# ESP32_LED_Matrix.net
KiCad netlist of a schematic drawn in Altium Designer
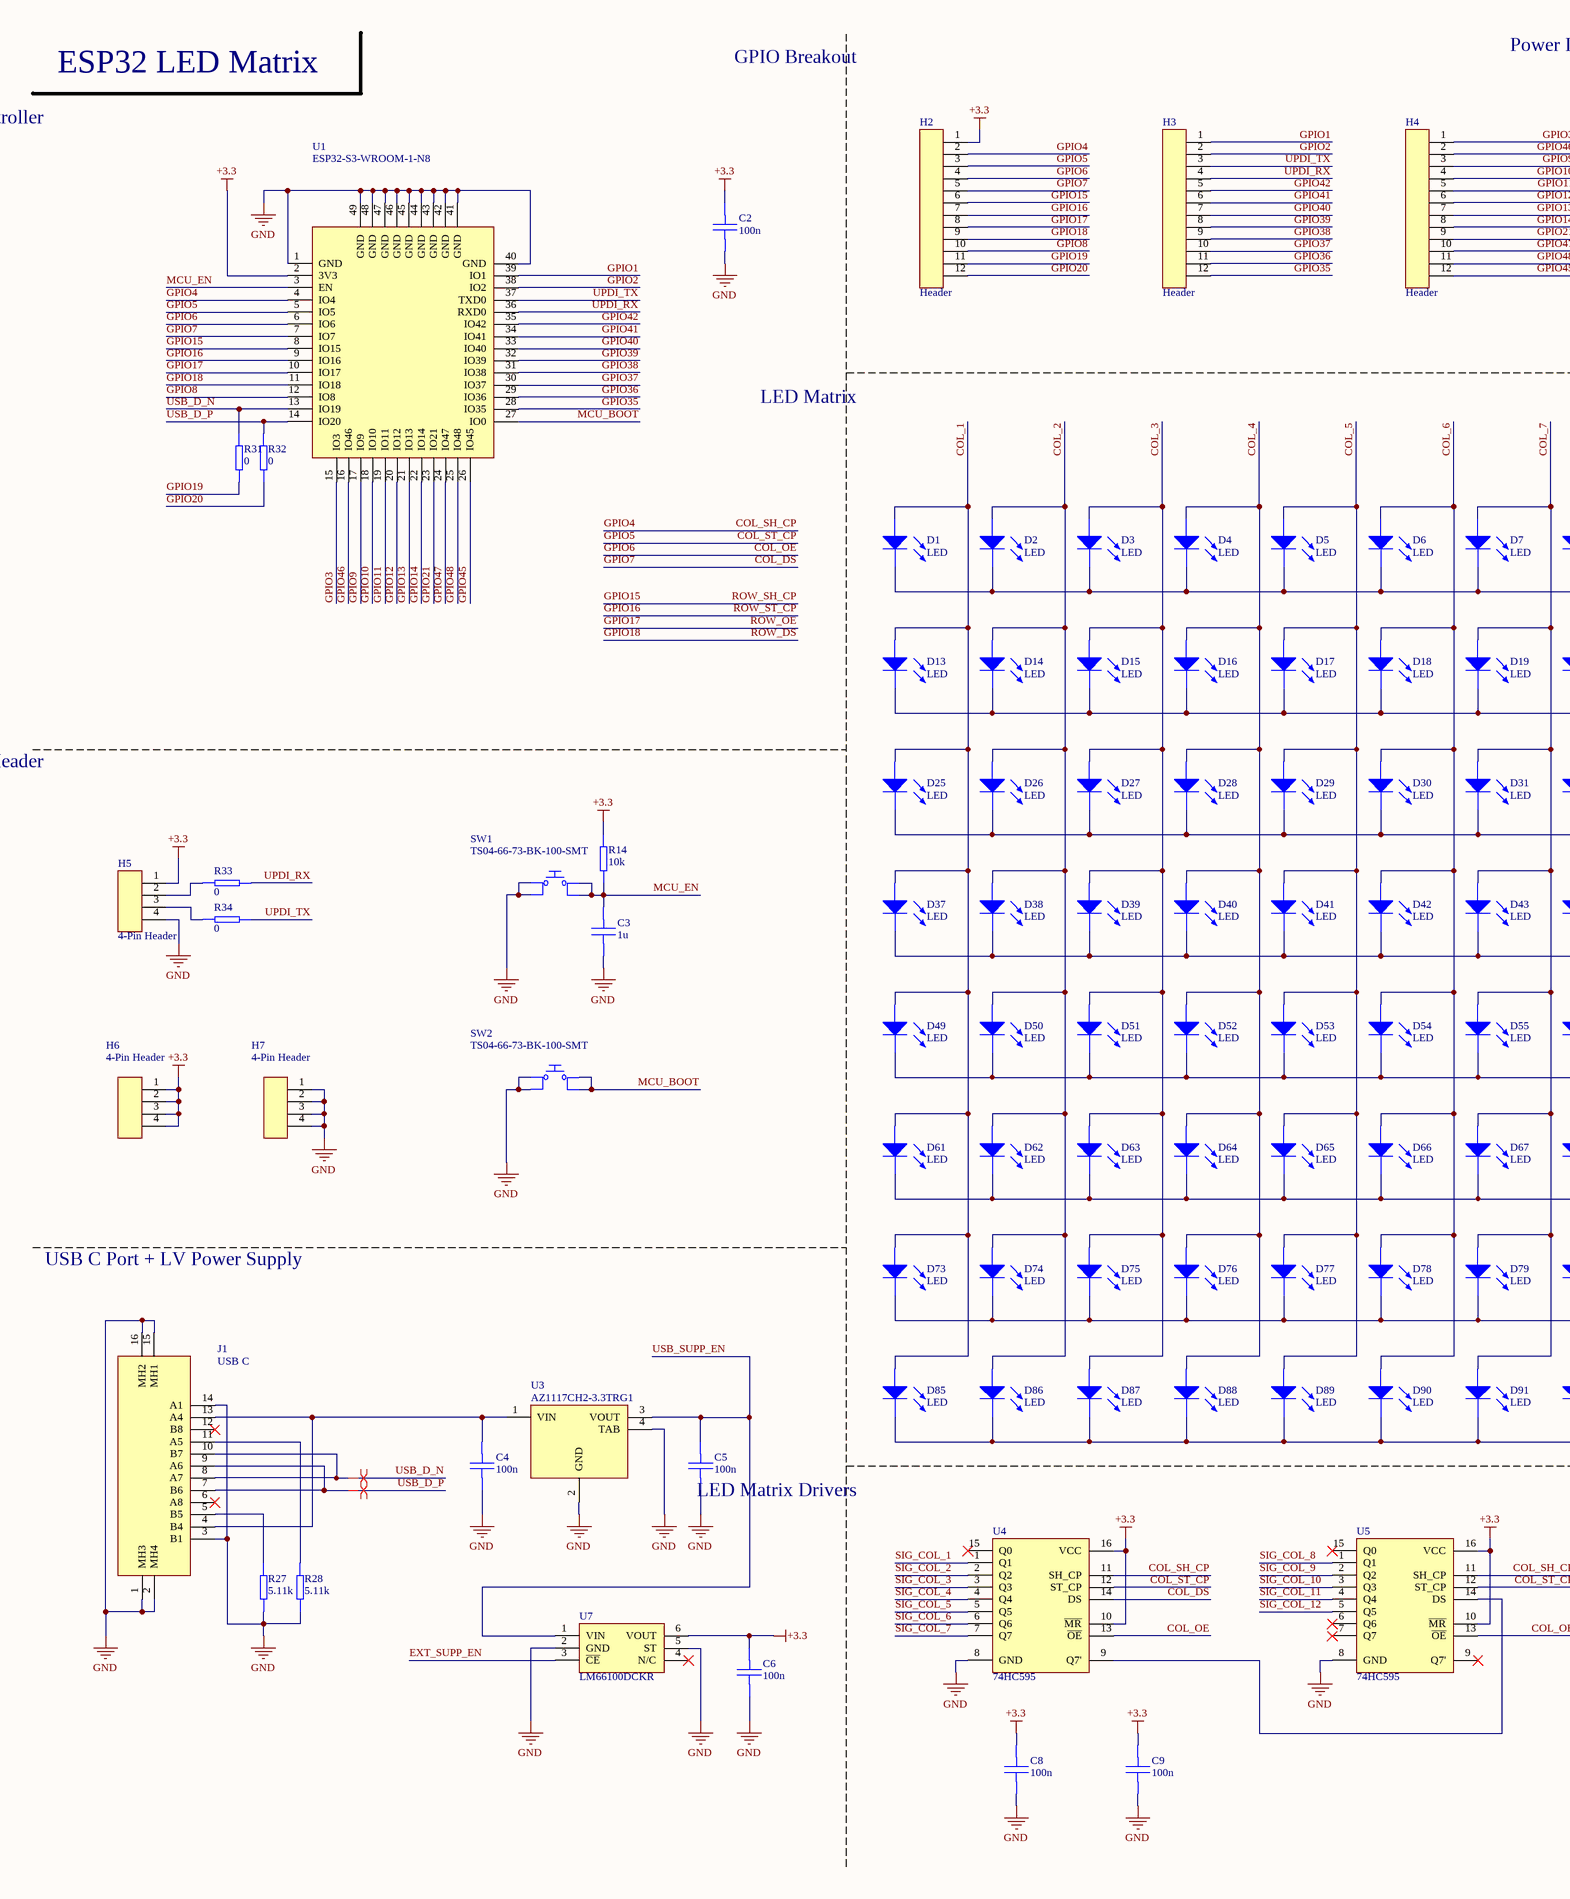
[diagram p0: ESP32_LED_Matrix.SchDoc, left]
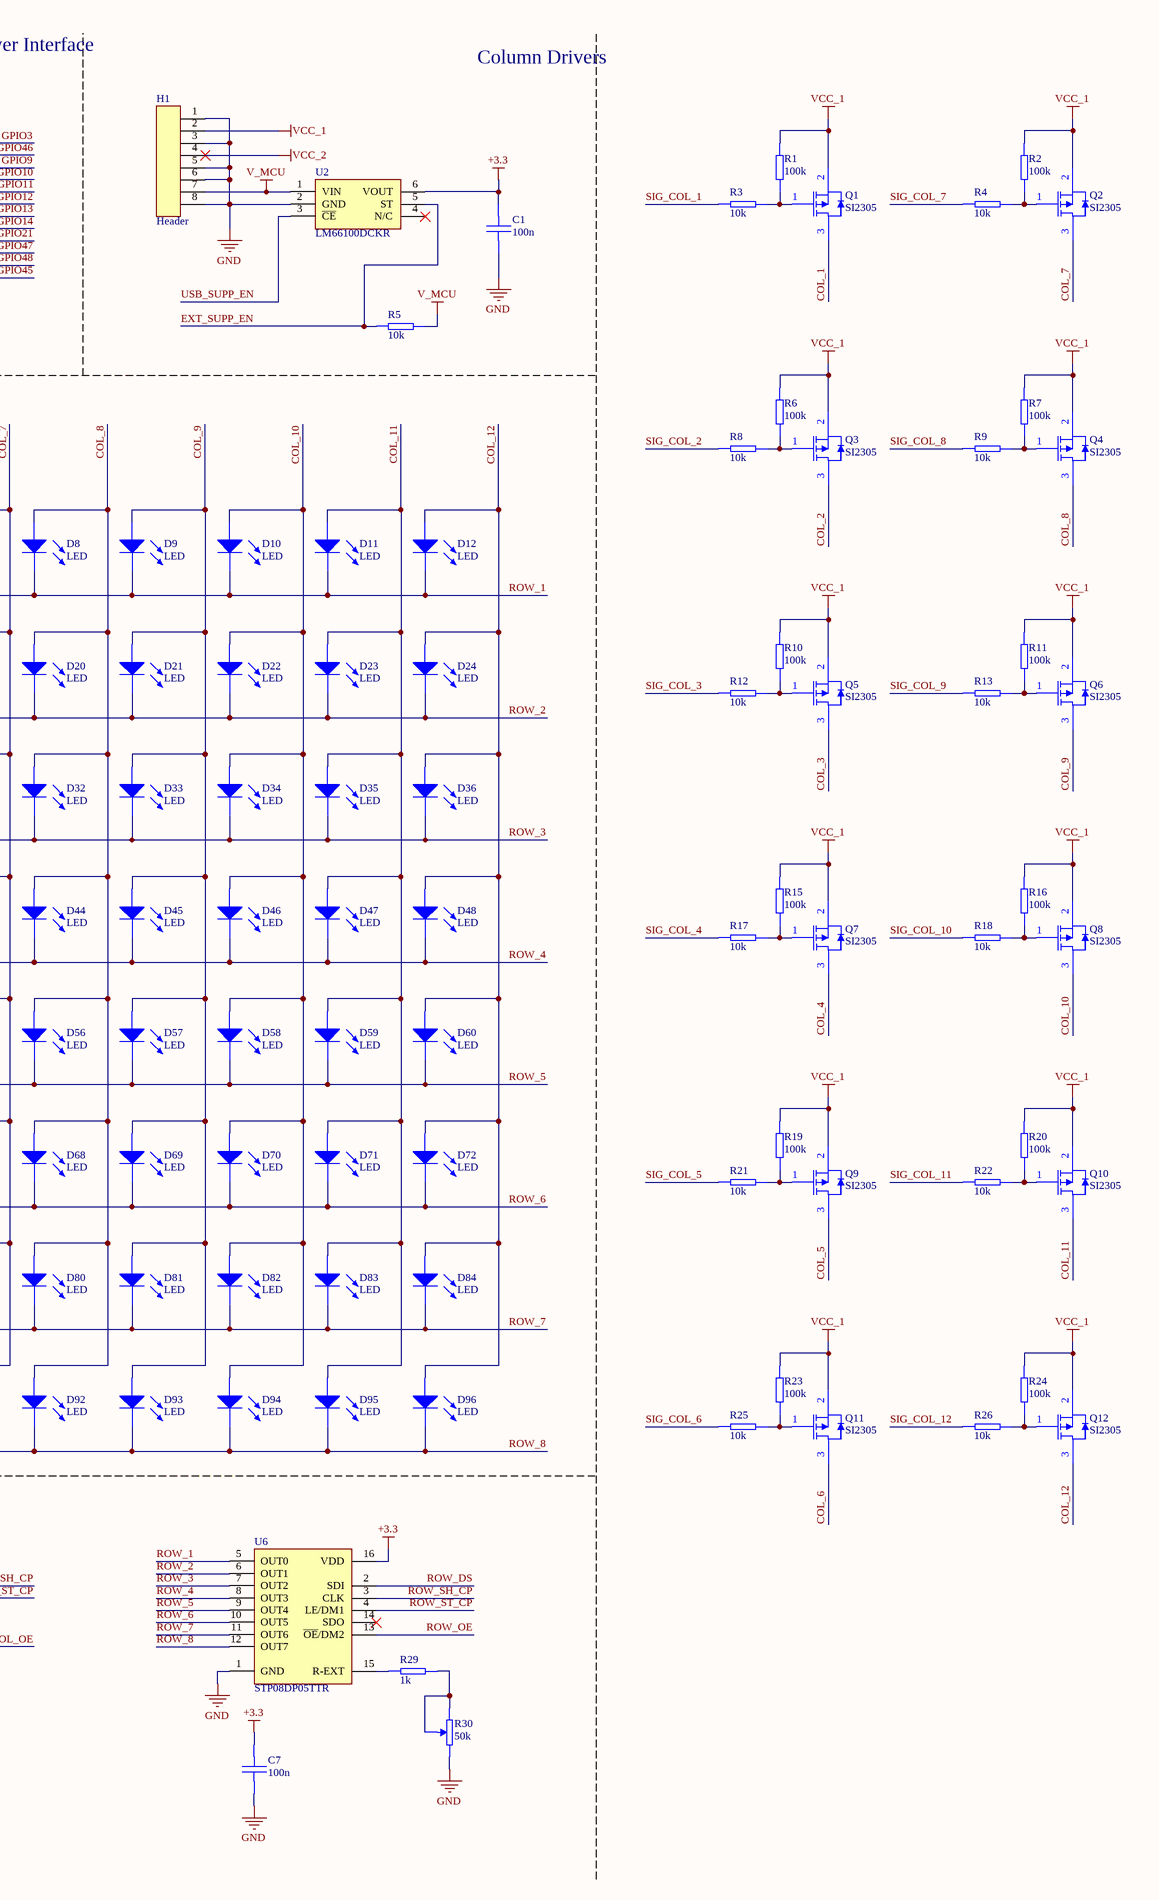
[diagram p1: ESP32_LED_Matrix.SchDoc, right]

(export (version "E")
  (design (tool "Eeschema 10.0.6"))
  (components
    (comp (ref "C1")
      (value "100n")
      (footprint "IEEE_Workshop_Footprints:CAP0805")
      (description "Non Polarized Capacitor")
      (libsource (lib "HT2.2") (part "Capacitor - Non Polarized"))
    )
    (comp (ref "C2")
      (value "100n")
      (footprint "IEEE_Workshop_Footprints:CAP0805")
      (description "Non Polarized Capacitor")
      (libsource (lib "HT2.2") (part "Capacitor - Non Polarized"))
    )
    (comp (ref "C3")
      (value "1u")
      (footprint "IEEE_Workshop_Footprints:CAP0805")
      (description "Non Polarized Capacitor")
      (libsource (lib "HT2.2") (part "Capacitor - Non Polarized"))
    )
    (comp (ref "C4")
      (value "100n")
      (footprint "IEEE_Workshop_Footprints:CAP0805")
      (description "Non Polarized Capacitor")
      (libsource (lib "TD") (part "Capacitor - Non Polarized"))
    )
    (comp (ref "C5")
      (value "100n")
      (footprint "IEEE_Workshop_Footprints:CAP0805")
      (description "Non Polarized Capacitor")
      (libsource (lib "HT2.2") (part "Capacitor - Non Polarized"))
    )
    (comp (ref "C6")
      (value "100n")
      (footprint "IEEE_Workshop_Footprints:CAP0805")
      (description "Non Polarized Capacitor")
      (libsource (lib "HT2.2") (part "Capacitor - Non Polarized"))
    )
    (comp (ref "C7")
      (value "100n")
      (footprint "IEEE_Workshop_Footprints:CAP0805")
      (description "Non Polarized Capacitor")
      (libsource (lib "TD") (part "Capacitor - Non Polarized"))
    )
    (comp (ref "C8")
      (value "100n")
      (footprint "IEEE_Workshop_Footprints:CAP0805")
      (description "Non Polarized Capacitor")
      (libsource (lib "TD") (part "Capacitor - Non Polarized"))
    )
    (comp (ref "C9")
      (value "100n")
      (footprint "IEEE_Workshop_Footprints:CAP0805")
      (description "Non Polarized Capacitor")
      (libsource (lib "TD") (part "Capacitor - Non Polarized"))
    )
    (comp (ref "D1")
      (value "LED")
      (footprint "IEEE_Workshop_Footprints:LEDM2012X80N")
      (description "General Purpose LED")
      (libsource (lib "TD") (part "LED"))
    )
    (comp (ref "D2")
      (value "LED")
      (footprint "IEEE_Workshop_Footprints:LEDM2012X80N")
      (description "General Purpose LED")
      (libsource (lib "TD") (part "LED"))
    )
    (comp (ref "D3")
      (value "LED")
      (footprint "IEEE_Workshop_Footprints:LEDM2012X80N")
      (description "General Purpose LED")
      (libsource (lib "TD") (part "LED"))
    )
    (comp (ref "D4")
      (value "LED")
      (footprint "IEEE_Workshop_Footprints:LEDM2012X80N")
      (description "General Purpose LED")
      (libsource (lib "TD") (part "LED"))
    )
    (comp (ref "D5")
      (value "LED")
      (footprint "IEEE_Workshop_Footprints:LEDM2012X80N")
      (description "General Purpose LED")
      (libsource (lib "TD") (part "LED"))
    )
    (comp (ref "D6")
      (value "LED")
      (footprint "IEEE_Workshop_Footprints:LEDM2012X80N")
      (description "General Purpose LED")
      (libsource (lib "TD") (part "LED"))
    )
    (comp (ref "D7")
      (value "LED")
      (footprint "IEEE_Workshop_Footprints:LEDM2012X80N")
      (description "General Purpose LED")
      (libsource (lib "TD") (part "LED"))
    )
    (comp (ref "D8")
      (value "LED")
      (footprint "IEEE_Workshop_Footprints:LEDM2012X80N")
      (description "General Purpose LED")
      (libsource (lib "TD") (part "LED"))
    )
    (comp (ref "D9")
      (value "LED")
      (footprint "IEEE_Workshop_Footprints:LEDM2012X80N")
      (description "General Purpose LED")
      (libsource (lib "TD") (part "LED"))
    )
    (comp (ref "D10")
      (value "LED")
      (footprint "IEEE_Workshop_Footprints:LEDM2012X80N")
      (description "General Purpose LED")
      (libsource (lib "TD") (part "LED"))
    )
    (comp (ref "D11")
      (value "LED")
      (footprint "IEEE_Workshop_Footprints:LEDM2012X80N")
      (description "General Purpose LED")
      (libsource (lib "TD") (part "LED"))
    )
    (comp (ref "D12")
      (value "LED")
      (footprint "IEEE_Workshop_Footprints:LEDM2012X80N")
      (description "General Purpose LED")
      (libsource (lib "TD") (part "LED"))
    )
    (comp (ref "D13")
      (value "LED")
      (footprint "IEEE_Workshop_Footprints:LEDM2012X80N")
      (description "General Purpose LED")
      (libsource (lib "TD") (part "LED"))
    )
    (comp (ref "D14")
      (value "LED")
      (footprint "IEEE_Workshop_Footprints:LEDM2012X80N")
      (description "General Purpose LED")
      (libsource (lib "TD") (part "LED"))
    )
    (comp (ref "D15")
      (value "LED")
      (footprint "IEEE_Workshop_Footprints:LEDM2012X80N")
      (description "General Purpose LED")
      (libsource (lib "TD") (part "LED"))
    )
    (comp (ref "D16")
      (value "LED")
      (footprint "IEEE_Workshop_Footprints:LEDM2012X80N")
      (description "General Purpose LED")
      (libsource (lib "TD") (part "LED"))
    )
    (comp (ref "D17")
      (value "LED")
      (footprint "IEEE_Workshop_Footprints:LEDM2012X80N")
      (description "General Purpose LED")
      (libsource (lib "TD") (part "LED"))
    )
    (comp (ref "D18")
      (value "LED")
      (footprint "IEEE_Workshop_Footprints:LEDM2012X80N")
      (description "General Purpose LED")
      (libsource (lib "TD") (part "LED"))
    )
    (comp (ref "D19")
      (value "LED")
      (footprint "IEEE_Workshop_Footprints:LEDM2012X80N")
      (description "General Purpose LED")
      (libsource (lib "TD") (part "LED"))
    )
    (comp (ref "D20")
      (value "LED")
      (footprint "IEEE_Workshop_Footprints:LEDM2012X80N")
      (description "General Purpose LED")
      (libsource (lib "TD") (part "LED"))
    )
    (comp (ref "D21")
      (value "LED")
      (footprint "IEEE_Workshop_Footprints:LEDM2012X80N")
      (description "General Purpose LED")
      (libsource (lib "TD") (part "LED"))
    )
    (comp (ref "D22")
      (value "LED")
      (footprint "IEEE_Workshop_Footprints:LEDM2012X80N")
      (description "General Purpose LED")
      (libsource (lib "TD") (part "LED"))
    )
    (comp (ref "D23")
      (value "LED")
      (footprint "IEEE_Workshop_Footprints:LEDM2012X80N")
      (description "General Purpose LED")
      (libsource (lib "TD") (part "LED"))
    )
    (comp (ref "D24")
      (value "LED")
      (footprint "IEEE_Workshop_Footprints:LEDM2012X80N")
      (description "General Purpose LED")
      (libsource (lib "TD") (part "LED"))
    )
    (comp (ref "D25")
      (value "LED")
      (footprint "IEEE_Workshop_Footprints:LEDM2012X80N")
      (description "General Purpose LED")
      (libsource (lib "TD") (part "LED"))
    )
    (comp (ref "D26")
      (value "LED")
      (footprint "IEEE_Workshop_Footprints:LEDM2012X80N")
      (description "General Purpose LED")
      (libsource (lib "TD") (part "LED"))
    )
    (comp (ref "D27")
      (value "LED")
      (footprint "IEEE_Workshop_Footprints:LEDM2012X80N")
      (description "General Purpose LED")
      (libsource (lib "TD") (part "LED"))
    )
    (comp (ref "D28")
      (value "LED")
      (footprint "IEEE_Workshop_Footprints:LEDM2012X80N")
      (description "General Purpose LED")
      (libsource (lib "TD") (part "LED"))
    )
    (comp (ref "D29")
      (value "LED")
      (footprint "IEEE_Workshop_Footprints:LEDM2012X80N")
      (description "General Purpose LED")
      (libsource (lib "TD") (part "LED"))
    )
    (comp (ref "D30")
      (value "LED")
      (footprint "IEEE_Workshop_Footprints:LEDM2012X80N")
      (description "General Purpose LED")
      (libsource (lib "TD") (part "LED"))
    )
    (comp (ref "D31")
      (value "LED")
      (footprint "IEEE_Workshop_Footprints:LEDM2012X80N")
      (description "General Purpose LED")
      (libsource (lib "TD") (part "LED"))
    )
    (comp (ref "D32")
      (value "LED")
      (footprint "IEEE_Workshop_Footprints:LEDM2012X80N")
      (description "General Purpose LED")
      (libsource (lib "TD") (part "LED"))
    )
    (comp (ref "D33")
      (value "LED")
      (footprint "IEEE_Workshop_Footprints:LEDM2012X80N")
      (description "General Purpose LED")
      (libsource (lib "TD") (part "LED"))
    )
    (comp (ref "D34")
      (value "LED")
      (footprint "IEEE_Workshop_Footprints:LEDM2012X80N")
      (description "General Purpose LED")
      (libsource (lib "TD") (part "LED"))
    )
    (comp (ref "D35")
      (value "LED")
      (footprint "IEEE_Workshop_Footprints:LEDM2012X80N")
      (description "General Purpose LED")
      (libsource (lib "TD") (part "LED"))
    )
    (comp (ref "D36")
      (value "LED")
      (footprint "IEEE_Workshop_Footprints:LEDM2012X80N")
      (description "General Purpose LED")
      (libsource (lib "TD") (part "LED"))
    )
    (comp (ref "D37")
      (value "LED")
      (footprint "IEEE_Workshop_Footprints:LEDM2012X80N")
      (description "General Purpose LED")
      (libsource (lib "TD") (part "LED"))
    )
    (comp (ref "D38")
      (value "LED")
      (footprint "IEEE_Workshop_Footprints:LEDM2012X80N")
      (description "General Purpose LED")
      (libsource (lib "TD") (part "LED"))
    )
    (comp (ref "D39")
      (value "LED")
      (footprint "IEEE_Workshop_Footprints:LEDM2012X80N")
      (description "General Purpose LED")
      (libsource (lib "TD") (part "LED"))
    )
    (comp (ref "D40")
      (value "LED")
      (footprint "IEEE_Workshop_Footprints:LEDM2012X80N")
      (description "General Purpose LED")
      (libsource (lib "TD") (part "LED"))
    )
    (comp (ref "D41")
      (value "LED")
      (footprint "IEEE_Workshop_Footprints:LEDM2012X80N")
      (description "General Purpose LED")
      (libsource (lib "TD") (part "LED"))
    )
    (comp (ref "D42")
      (value "LED")
      (footprint "IEEE_Workshop_Footprints:LEDM2012X80N")
      (description "General Purpose LED")
      (libsource (lib "TD") (part "LED"))
    )
    (comp (ref "D43")
      (value "LED")
      (footprint "IEEE_Workshop_Footprints:LEDM2012X80N")
      (description "General Purpose LED")
      (libsource (lib "TD") (part "LED"))
    )
    (comp (ref "D44")
      (value "LED")
      (footprint "IEEE_Workshop_Footprints:LEDM2012X80N")
      (description "General Purpose LED")
      (libsource (lib "TD") (part "LED"))
    )
    (comp (ref "D45")
      (value "LED")
      (footprint "IEEE_Workshop_Footprints:LEDM2012X80N")
      (description "General Purpose LED")
      (libsource (lib "TD") (part "LED"))
    )
    (comp (ref "D46")
      (value "LED")
      (footprint "IEEE_Workshop_Footprints:LEDM2012X80N")
      (description "General Purpose LED")
      (libsource (lib "TD") (part "LED"))
    )
    (comp (ref "D47")
      (value "LED")
      (footprint "IEEE_Workshop_Footprints:LEDM2012X80N")
      (description "General Purpose LED")
      (libsource (lib "TD") (part "LED"))
    )
    (comp (ref "D48")
      (value "LED")
      (footprint "IEEE_Workshop_Footprints:LEDM2012X80N")
      (description "General Purpose LED")
      (libsource (lib "TD") (part "LED"))
    )
    (comp (ref "D49")
      (value "LED")
      (footprint "IEEE_Workshop_Footprints:LEDM2012X80N")
      (description "General Purpose LED")
      (libsource (lib "TD") (part "LED"))
    )
    (comp (ref "D50")
      (value "LED")
      (footprint "IEEE_Workshop_Footprints:LEDM2012X80N")
      (description "General Purpose LED")
      (libsource (lib "TD") (part "LED"))
    )
    (comp (ref "D51")
      (value "LED")
      (footprint "IEEE_Workshop_Footprints:LEDM2012X80N")
      (description "General Purpose LED")
      (libsource (lib "TD") (part "LED"))
    )
    (comp (ref "D52")
      (value "LED")
      (footprint "IEEE_Workshop_Footprints:LEDM2012X80N")
      (description "General Purpose LED")
      (libsource (lib "TD") (part "LED"))
    )
    (comp (ref "D53")
      (value "LED")
      (footprint "IEEE_Workshop_Footprints:LEDM2012X80N")
      (description "General Purpose LED")
      (libsource (lib "TD") (part "LED"))
    )
    (comp (ref "D54")
      (value "LED")
      (footprint "IEEE_Workshop_Footprints:LEDM2012X80N")
      (description "General Purpose LED")
      (libsource (lib "TD") (part "LED"))
    )
    (comp (ref "D55")
      (value "LED")
      (footprint "IEEE_Workshop_Footprints:LEDM2012X80N")
      (description "General Purpose LED")
      (libsource (lib "TD") (part "LED"))
    )
    (comp (ref "D56")
      (value "LED")
      (footprint "IEEE_Workshop_Footprints:LEDM2012X80N")
      (description "General Purpose LED")
      (libsource (lib "TD") (part "LED"))
    )
    (comp (ref "D57")
      (value "LED")
      (footprint "IEEE_Workshop_Footprints:LEDM2012X80N")
      (description "General Purpose LED")
      (libsource (lib "TD") (part "LED"))
    )
    (comp (ref "D58")
      (value "LED")
      (footprint "IEEE_Workshop_Footprints:LEDM2012X80N")
      (description "General Purpose LED")
      (libsource (lib "TD") (part "LED"))
    )
    (comp (ref "D59")
      (value "LED")
      (footprint "IEEE_Workshop_Footprints:LEDM2012X80N")
      (description "General Purpose LED")
      (libsource (lib "TD") (part "LED"))
    )
    (comp (ref "D60")
      (value "LED")
      (footprint "IEEE_Workshop_Footprints:LEDM2012X80N")
      (description "General Purpose LED")
      (libsource (lib "TD") (part "LED"))
    )
    (comp (ref "D61")
      (value "LED")
      (footprint "IEEE_Workshop_Footprints:LEDM2012X80N")
      (description "General Purpose LED")
      (libsource (lib "TD") (part "LED"))
    )
    (comp (ref "D62")
      (value "LED")
      (footprint "IEEE_Workshop_Footprints:LEDM2012X80N")
      (description "General Purpose LED")
      (libsource (lib "TD") (part "LED"))
    )
    (comp (ref "D63")
      (value "LED")
      (footprint "IEEE_Workshop_Footprints:LEDM2012X80N")
      (description "General Purpose LED")
      (libsource (lib "TD") (part "LED"))
    )
    (comp (ref "D64")
      (value "LED")
      (footprint "IEEE_Workshop_Footprints:LEDM2012X80N")
      (description "General Purpose LED")
      (libsource (lib "TD") (part "LED"))
    )
    (comp (ref "D65")
      (value "LED")
      (footprint "IEEE_Workshop_Footprints:LEDM2012X80N")
      (description "General Purpose LED")
      (libsource (lib "TD") (part "LED"))
    )
    (comp (ref "D66")
      (value "LED")
      (footprint "IEEE_Workshop_Footprints:LEDM2012X80N")
      (description "General Purpose LED")
      (libsource (lib "TD") (part "LED"))
    )
    (comp (ref "D67")
      (value "LED")
      (footprint "IEEE_Workshop_Footprints:LEDM2012X80N")
      (description "General Purpose LED")
      (libsource (lib "TD") (part "LED"))
    )
    (comp (ref "D68")
      (value "LED")
      (footprint "IEEE_Workshop_Footprints:LEDM2012X80N")
      (description "General Purpose LED")
      (libsource (lib "TD") (part "LED"))
    )
    (comp (ref "D69")
      (value "LED")
      (footprint "IEEE_Workshop_Footprints:LEDM2012X80N")
      (description "General Purpose LED")
      (libsource (lib "TD") (part "LED"))
    )
    (comp (ref "D70")
      (value "LED")
      (footprint "IEEE_Workshop_Footprints:LEDM2012X80N")
      (description "General Purpose LED")
      (libsource (lib "TD") (part "LED"))
    )
    (comp (ref "D71")
      (value "LED")
      (footprint "IEEE_Workshop_Footprints:LEDM2012X80N")
      (description "General Purpose LED")
      (libsource (lib "TD") (part "LED"))
    )
    (comp (ref "D72")
      (value "LED")
      (footprint "IEEE_Workshop_Footprints:LEDM2012X80N")
      (description "General Purpose LED")
      (libsource (lib "TD") (part "LED"))
    )
    (comp (ref "D73")
      (value "LED")
      (footprint "IEEE_Workshop_Footprints:LEDM2012X80N")
      (description "General Purpose LED")
      (libsource (lib "TD") (part "LED"))
    )
    (comp (ref "D74")
      (value "LED")
      (footprint "IEEE_Workshop_Footprints:LEDM2012X80N")
      (description "General Purpose LED")
      (libsource (lib "TD") (part "LED"))
    )
    (comp (ref "D75")
      (value "LED")
      (footprint "IEEE_Workshop_Footprints:LEDM2012X80N")
      (description "General Purpose LED")
      (libsource (lib "TD") (part "LED"))
    )
    (comp (ref "D76")
      (value "LED")
      (footprint "IEEE_Workshop_Footprints:LEDM2012X80N")
      (description "General Purpose LED")
      (libsource (lib "TD") (part "LED"))
    )
    (comp (ref "D77")
      (value "LED")
      (footprint "IEEE_Workshop_Footprints:LEDM2012X80N")
      (description "General Purpose LED")
      (libsource (lib "TD") (part "LED"))
    )
    (comp (ref "D78")
      (value "LED")
      (footprint "IEEE_Workshop_Footprints:LEDM2012X80N")
      (description "General Purpose LED")
      (libsource (lib "TD") (part "LED"))
    )
    (comp (ref "D79")
      (value "LED")
      (footprint "IEEE_Workshop_Footprints:LEDM2012X80N")
      (description "General Purpose LED")
      (libsource (lib "TD") (part "LED"))
    )
    (comp (ref "D80")
      (value "LED")
      (footprint "IEEE_Workshop_Footprints:LEDM2012X80N")
      (description "General Purpose LED")
      (libsource (lib "TD") (part "LED"))
    )
    (comp (ref "D81")
      (value "LED")
      (footprint "IEEE_Workshop_Footprints:LEDM2012X80N")
      (description "General Purpose LED")
      (libsource (lib "TD") (part "LED"))
    )
    (comp (ref "D82")
      (value "LED")
      (footprint "IEEE_Workshop_Footprints:LEDM2012X80N")
      (description "General Purpose LED")
      (libsource (lib "TD") (part "LED"))
    )
    (comp (ref "D83")
      (value "LED")
      (footprint "IEEE_Workshop_Footprints:LEDM2012X80N")
      (description "General Purpose LED")
      (libsource (lib "TD") (part "LED"))
    )
    (comp (ref "D84")
      (value "LED")
      (footprint "IEEE_Workshop_Footprints:LEDM2012X80N")
      (description "General Purpose LED")
      (libsource (lib "TD") (part "LED"))
    )
    (comp (ref "D85")
      (value "LED")
      (footprint "IEEE_Workshop_Footprints:LEDM2012X80N")
      (description "General Purpose LED")
      (libsource (lib "TD") (part "LED"))
    )
    (comp (ref "D86")
      (value "LED")
      (footprint "IEEE_Workshop_Footprints:LEDM2012X80N")
      (description "General Purpose LED")
      (libsource (lib "TD") (part "LED"))
    )
    (comp (ref "D87")
      (value "LED")
      (footprint "IEEE_Workshop_Footprints:LEDM2012X80N")
      (description "General Purpose LED")
      (libsource (lib "TD") (part "LED"))
    )
    (comp (ref "D88")
      (value "LED")
      (footprint "IEEE_Workshop_Footprints:LEDM2012X80N")
      (description "General Purpose LED")
      (libsource (lib "TD") (part "LED"))
    )
    (comp (ref "D89")
      (value "LED")
      (footprint "IEEE_Workshop_Footprints:LEDM2012X80N")
      (description "General Purpose LED")
      (libsource (lib "TD") (part "LED"))
    )
    (comp (ref "D90")
      (value "LED")
      (footprint "IEEE_Workshop_Footprints:LEDM2012X80N")
      (description "General Purpose LED")
      (libsource (lib "TD") (part "LED"))
    )
    (comp (ref "D91")
      (value "LED")
      (footprint "IEEE_Workshop_Footprints:LEDM2012X80N")
      (description "General Purpose LED")
      (libsource (lib "TD") (part "LED"))
    )
    (comp (ref "D92")
      (value "LED")
      (footprint "IEEE_Workshop_Footprints:LEDM2012X80N")
      (description "General Purpose LED")
      (libsource (lib "TD") (part "LED"))
    )
    (comp (ref "D93")
      (value "LED")
      (footprint "IEEE_Workshop_Footprints:LEDM2012X80N")
      (description "General Purpose LED")
      (libsource (lib "TD") (part "LED"))
    )
    (comp (ref "D94")
      (value "LED")
      (footprint "IEEE_Workshop_Footprints:LEDM2012X80N")
      (description "General Purpose LED")
      (libsource (lib "TD") (part "LED"))
    )
    (comp (ref "D95")
      (value "LED")
      (footprint "IEEE_Workshop_Footprints:LEDM2012X80N")
      (description "General Purpose LED")
      (libsource (lib "TD") (part "LED"))
    )
    (comp (ref "D96")
      (value "LED")
      (footprint "IEEE_Workshop_Footprints:LEDM2012X80N")
      (description "General Purpose LED")
      (libsource (lib "TD") (part "LED"))
    )
    (comp (ref "H1")
      (value "Header")
      (footprint "IEEE_Workshop_Footprints:Header_1X8")
      (description "8-Pin Header")
      (libsource (lib "TD") (part "8-Pin Header"))
    )
    (comp (ref "H2")
      (value "Header")
      (footprint "IEEE_Workshop_Footprints:Header_1X12")
      (description "12-Pin Header")
      (libsource (lib "TD") (part "12-Pin Header"))
    )
    (comp (ref "H3")
      (value "Header")
      (footprint "IEEE_Workshop_Footprints:Header_1X12")
      (description "12-Pin Header")
      (libsource (lib "TD") (part "12-Pin Header"))
    )
    (comp (ref "H4")
      (value "Header")
      (footprint "IEEE_Workshop_Footprints:Header_1X12")
      (description "12-Pin Header")
      (libsource (lib "TD") (part "12-Pin Header"))
    )
    (comp (ref "H5")
      (value "4-Pin Header")
      (footprint "IEEE_Workshop_Footprints:Header_1X4")
      (libsource (lib "TD") (part "4-Pin Header"))
    )
    (comp (ref "H6")
      (value "4-Pin Header")
      (footprint "IEEE_Workshop_Footprints:Header_1X4")
      (libsource (lib "TD") (part "4-Pin Header"))
    )
    (comp (ref "H7")
      (value "4-Pin Header")
      (footprint "IEEE_Workshop_Footprints:Header_1X4")
      (libsource (lib "TD") (part "4-Pin Header"))
    )
    (comp (ref "J1")
      (value "USB C")
      (footprint "IEEE_Workshop_Footprints:USB TYPE C 12 PIN")
      (libsource (lib "TD") (part "USB Type C Connector 12 Pin"))
    )
    (comp (ref "Q1")
      (value "SI2305")
      (footprint "IEEE_Workshop_Footprints:SOT23")
      (description "General Purpose P-Channel MOSFET")
      (libsource (lib "TD") (part "SI2305"))
    )
    (comp (ref "Q2")
      (value "SI2305")
      (footprint "IEEE_Workshop_Footprints:SOT23")
      (description "General Purpose P-Channel MOSFET")
      (libsource (lib "TD") (part "SI2305"))
    )
    (comp (ref "Q3")
      (value "SI2305")
      (footprint "IEEE_Workshop_Footprints:SOT23")
      (description "General Purpose P-Channel MOSFET")
      (libsource (lib "TD") (part "SI2305"))
    )
    (comp (ref "Q4")
      (value "SI2305")
      (footprint "IEEE_Workshop_Footprints:SOT23")
      (description "General Purpose P-Channel MOSFET")
      (libsource (lib "TD") (part "SI2305"))
    )
    (comp (ref "Q5")
      (value "SI2305")
      (footprint "IEEE_Workshop_Footprints:SOT23")
      (description "General Purpose P-Channel MOSFET")
      (libsource (lib "TD") (part "SI2305"))
    )
    (comp (ref "Q6")
      (value "SI2305")
      (footprint "IEEE_Workshop_Footprints:SOT23")
      (description "General Purpose P-Channel MOSFET")
      (libsource (lib "TD") (part "SI2305"))
    )
    (comp (ref "Q7")
      (value "SI2305")
      (footprint "IEEE_Workshop_Footprints:SOT23")
      (description "General Purpose P-Channel MOSFET")
      (libsource (lib "TD") (part "SI2305"))
    )
    (comp (ref "Q8")
      (value "SI2305")
      (footprint "IEEE_Workshop_Footprints:SOT23")
      (description "General Purpose P-Channel MOSFET")
      (libsource (lib "TD") (part "SI2305"))
    )
    (comp (ref "Q9")
      (value "SI2305")
      (footprint "IEEE_Workshop_Footprints:SOT23")
      (description "General Purpose P-Channel MOSFET")
      (libsource (lib "TD") (part "SI2305"))
    )
    (comp (ref "Q10")
      (value "SI2305")
      (footprint "IEEE_Workshop_Footprints:SOT23")
      (description "General Purpose P-Channel MOSFET")
      (libsource (lib "TD") (part "SI2305"))
    )
    (comp (ref "Q11")
      (value "SI2305")
      (footprint "IEEE_Workshop_Footprints:SOT23")
      (description "General Purpose P-Channel MOSFET")
      (libsource (lib "TD") (part "SI2305"))
    )
    (comp (ref "Q12")
      (value "SI2305")
      (footprint "IEEE_Workshop_Footprints:SOT23")
      (description "General Purpose P-Channel MOSFET")
      (libsource (lib "TD") (part "SI2305"))
    )
    (comp (ref "R1")
      (value "100k")
      (footprint "IEEE_Workshop_Footprints:RESC0805")
      (description "Resistor")
      (libsource (lib "TD") (part "Resistor"))
    )
    (comp (ref "R2")
      (value "100k")
      (footprint "IEEE_Workshop_Footprints:RESC0805")
      (description "Resistor")
      (libsource (lib "TD") (part "Resistor"))
    )
    (comp (ref "R3")
      (value "10k")
      (footprint "IEEE_Workshop_Footprints:RESC0805")
      (description "Resistor")
      (libsource (lib "TD") (part "Resistor"))
    )
    (comp (ref "R4")
      (value "10k")
      (footprint "IEEE_Workshop_Footprints:RESC0805")
      (description "Resistor")
      (libsource (lib "TD") (part "Resistor"))
    )
    (comp (ref "R5")
      (value "10k")
      (footprint "IEEE_Workshop_Footprints:RESC0805")
      (description "Resistor")
      (libsource (lib "TD") (part "Resistor"))
    )
    (comp (ref "R6")
      (value "100k")
      (footprint "IEEE_Workshop_Footprints:RESC0805")
      (description "Resistor")
      (libsource (lib "TD") (part "Resistor"))
    )
    (comp (ref "R7")
      (value "100k")
      (footprint "IEEE_Workshop_Footprints:RESC0805")
      (description "Resistor")
      (libsource (lib "TD") (part "Resistor"))
    )
    (comp (ref "R8")
      (value "10k")
      (footprint "IEEE_Workshop_Footprints:RESC0805")
      (description "Resistor")
      (libsource (lib "TD") (part "Resistor"))
    )
    (comp (ref "R9")
      (value "10k")
      (footprint "IEEE_Workshop_Footprints:RESC0805")
      (description "Resistor")
      (libsource (lib "TD") (part "Resistor"))
    )
    (comp (ref "R10")
      (value "100k")
      (footprint "IEEE_Workshop_Footprints:RESC0805")
      (description "Resistor")
      (libsource (lib "TD") (part "Resistor"))
    )
    (comp (ref "R11")
      (value "100k")
      (footprint "IEEE_Workshop_Footprints:RESC0805")
      (description "Resistor")
      (libsource (lib "TD") (part "Resistor"))
    )
    (comp (ref "R12")
      (value "10k")
      (footprint "IEEE_Workshop_Footprints:RESC0805")
      (description "Resistor")
      (libsource (lib "TD") (part "Resistor"))
    )
    (comp (ref "R13")
      (value "10k")
      (footprint "IEEE_Workshop_Footprints:RESC0805")
      (description "Resistor")
      (libsource (lib "TD") (part "Resistor"))
    )
    (comp (ref "R14")
      (value "10k")
      (footprint "IEEE_Workshop_Footprints:RESC0805")
      (description "Resistor")
      (libsource (lib "TD") (part "Resistor"))
    )
    (comp (ref "R15")
      (value "100k")
      (footprint "IEEE_Workshop_Footprints:RESC0805")
      (description "Resistor")
      (libsource (lib "TD") (part "Resistor"))
    )
    (comp (ref "R16")
      (value "100k")
      (footprint "IEEE_Workshop_Footprints:RESC0805")
      (description "Resistor")
      (libsource (lib "TD") (part "Resistor"))
    )
    (comp (ref "R17")
      (value "10k")
      (footprint "IEEE_Workshop_Footprints:RESC0805")
      (description "Resistor")
      (libsource (lib "TD") (part "Resistor"))
    )
    (comp (ref "R18")
      (value "10k")
      (footprint "IEEE_Workshop_Footprints:RESC0805")
      (description "Resistor")
      (libsource (lib "TD") (part "Resistor"))
    )
    (comp (ref "R19")
      (value "100k")
      (footprint "IEEE_Workshop_Footprints:RESC0805")
      (description "Resistor")
      (libsource (lib "TD") (part "Resistor"))
    )
    (comp (ref "R20")
      (value "100k")
      (footprint "IEEE_Workshop_Footprints:RESC0805")
      (description "Resistor")
      (libsource (lib "TD") (part "Resistor"))
    )
    (comp (ref "R21")
      (value "10k")
      (footprint "IEEE_Workshop_Footprints:RESC0805")
      (description "Resistor")
      (libsource (lib "TD") (part "Resistor"))
    )
    (comp (ref "R22")
      (value "10k")
      (footprint "IEEE_Workshop_Footprints:RESC0805")
      (description "Resistor")
      (libsource (lib "TD") (part "Resistor"))
    )
    (comp (ref "R23")
      (value "100k")
      (footprint "IEEE_Workshop_Footprints:RESC0805")
      (description "Resistor")
      (libsource (lib "TD") (part "Resistor"))
    )
    (comp (ref "R24")
      (value "100k")
      (footprint "IEEE_Workshop_Footprints:RESC0805")
      (description "Resistor")
      (libsource (lib "TD") (part "Resistor"))
    )
    (comp (ref "R25")
      (value "10k")
      (footprint "IEEE_Workshop_Footprints:RESC0805")
      (description "Resistor")
      (libsource (lib "TD") (part "Resistor"))
    )
    (comp (ref "R26")
      (value "10k")
      (footprint "IEEE_Workshop_Footprints:RESC0805")
      (description "Resistor")
      (libsource (lib "TD") (part "Resistor"))
    )
    (comp (ref "R27")
      (value "5.11k")
      (footprint "IEEE_Workshop_Footprints:RESC0805")
      (description "Resistor")
      (libsource (lib "HT2.2") (part "Resistor"))
    )
    (comp (ref "R28")
      (value "5.11k")
      (footprint "IEEE_Workshop_Footprints:RESC0805")
      (description "Resistor")
      (libsource (lib "HT2.2") (part "Resistor"))
    )
    (comp (ref "R29")
      (value "1k")
      (footprint "IEEE_Workshop_Footprints:RESC0805")
      (description "Resistor")
      (libsource (lib "TD") (part "Resistor"))
    )
    (comp (ref "R30")
      (value "50k")
      (footprint "IEEE_Workshop_Footprints:3339P1103LF")
      (description "Potentionmeter")
      (libsource (lib "TD") (part "Potentiometer"))
    )
    (comp (ref "R31") (value "0") (description "Resistor") (libsource (lib "TD") (part "Resistor")))
    (comp (ref "R32") (value "0") (description "Resistor") (libsource (lib "TD") (part "Resistor")))
    (comp (ref "R33") (value "0") (description "Resistor") (libsource (lib "TD") (part "Resistor")))
    (comp (ref "R34") (value "0") (description "Resistor") (libsource (lib "TD") (part "Resistor")))
    (comp (ref "SW1")
      (value "TS04-66-73-BK-100-SMT")
      (footprint "IEEE_Workshop_Footprints:Tactile Button 6.0mm x 6.0mm")
      (description "Switch")
      (fields (field (name "MOUSER PART NUMBER") "179-TS046673BK100SMT"))
      (libsource (lib "TD") (part "TS04-66-73-BK-100-SMT"))
    )
    (comp (ref "SW2")
      (value "TS04-66-73-BK-100-SMT")
      (footprint "IEEE_Workshop_Footprints:Tactile Button 6.0mm x 6.0mm")
      (description "Switch")
      (fields (field (name "MOUSER PART NUMBER") "179-TS046673BK100SMT"))
      (libsource (lib "TD") (part "TS04-66-73-BK-100-SMT"))
    )
    (comp (ref "U1")
      (value "ESP32-S3-WROOM-1-N8")
      (footprint "IEEE_Workshop_Footprints:ESP32-S3-WROOM-1-N8")
      (description "ESP32 Microcontroller with Bluetooth and Wifi")
      (libsource (lib "HT2.3") (part "ESP32-S3-WROOM-1-N8"))
    )
    (comp (ref "U2")
      (value "LM66100DCKR")
      (footprint "IEEE_Workshop_Footprints:SC70-6")
      (description "5.5-V, 1.5-A 79-mΩ, Low IQ Ideal Diode With Input Polarity Protection")
      (fields (field (name "MOUSER PART NUMBER") "595-LM66100DCKR"))
      (libsource (lib "TD") (part "LM66100DCKR"))
    )
    (comp (ref "U3")
      (value "AZ1117CH2-3.3TRG1")
      (footprint "IEEE_Workshop_Footprints:SOT223")
      (description "3.3V Linear Voltage Regulator")
      (libsource (lib "TD") (part "AZ1117CH2-3.3TRG1_1"))
    )
    (comp (ref "U4")
      (value "74HC595")
      (footprint "IEEE_Workshop_Footprints:TSSOP16")
      (description "Shift Register")
      (libsource (lib "TD") (part "74HC595"))
    )
    (comp (ref "U5")
      (value "74HC595")
      (footprint "IEEE_Workshop_Footprints:TSSOP16")
      (description "Shift Register")
      (libsource (lib "TD") (part "74HC595"))
    )
    (comp (ref "U6")
      (value "STP08DP05TTR")
      (footprint "IEEE_Workshop_Footprints:TSSOP16")
      (description "LED Driver")
      (fields (field (name "MOUSER PART NUMBER") "511-STP08DP05TTR"))
      (libsource (lib "TD") (part "STP08DP05TTR"))
    )
    (comp (ref "U7")
      (value "LM66100DCKR")
      (footprint "IEEE_Workshop_Footprints:SC70-6")
      (description "5.5-V, 1.5-A 79-mΩ, Low IQ Ideal Diode With Input Polarity Protection")
      (fields (field (name "MOUSER PART NUMBER") "595-LM66100DCKR"))
      (libsource (lib "TD") (part "LM66100DCKR"))
    )
  )
  (nets
    (net (code "1") (name "+3.3") (class "Default")
      (node (ref "C1") (pin "1") (pintype "passive"))
      (node (ref "C2") (pin "1") (pintype "passive"))
      (node (ref "C6") (pin "1") (pintype "passive"))
      (node (ref "C7") (pin "1") (pintype "passive"))
      (node (ref "C8") (pin "1") (pintype "passive"))
      (node (ref "C9") (pin "1") (pintype "passive"))
      (node (ref "H2") (pin "1") (pintype "passive"))
      (node (ref "H5") (pin "1") (pintype "passive"))
      (node (ref "H6") (pin "1") (pintype "passive"))
      (node (ref "H6") (pin "2") (pintype "passive"))
      (node (ref "H6") (pin "3") (pintype "passive"))
      (node (ref "H6") (pin "4") (pintype "passive"))
      (node (ref "R14") (pin "1") (pintype "passive"))
      (node (ref "U1") (pin "2") (pinfunction "3V3_2") (pintype "passive"))
      (node (ref "U2") (pin "6") (pinfunction "VOUT_6") (pintype "passive"))
      (node (ref "U4") (pin "10") (pinfunction "~{MR}_10") (pintype "passive"))
      (node (ref "U4") (pin "16") (pinfunction "VCC_16") (pintype "passive"))
      (node (ref "U5") (pin "10") (pinfunction "~{MR}_10") (pintype "passive"))
      (node (ref "U5") (pin "16") (pinfunction "VCC_16") (pintype "passive"))
      (node (ref "U6") (pin "16") (pinfunction "VDD_16") (pintype "passive"))
      (node (ref "U7") (pin "6") (pinfunction "VOUT_6") (pintype "passive"))
    )
    (net (code "2") (name "/COL_1") (class "Default")
      (node (ref "D1") (pin "2") (pinfunction "A_2") (pintype "passive"))
      (node (ref "D13") (pin "2") (pinfunction "A_2") (pintype "passive"))
      (node (ref "D25") (pin "2") (pinfunction "A_2") (pintype "passive"))
      (node (ref "D37") (pin "2") (pinfunction "A_2") (pintype "passive"))
      (node (ref "D49") (pin "2") (pinfunction "A_2") (pintype "passive"))
      (node (ref "D61") (pin "2") (pinfunction "A_2") (pintype "passive"))
      (node (ref "D73") (pin "2") (pinfunction "A_2") (pintype "passive"))
      (node (ref "D85") (pin "2") (pinfunction "A_2") (pintype "passive"))
      (node (ref "Q1") (pin "3") (pinfunction "D_3") (pintype "passive"))
    )
    (net (code "3") (name "/COL_2") (class "Default")
      (node (ref "D14") (pin "2") (pinfunction "A_2") (pintype "passive"))
      (node (ref "D2") (pin "2") (pinfunction "A_2") (pintype "passive"))
      (node (ref "D26") (pin "2") (pinfunction "A_2") (pintype "passive"))
      (node (ref "D38") (pin "2") (pinfunction "A_2") (pintype "passive"))
      (node (ref "D50") (pin "2") (pinfunction "A_2") (pintype "passive"))
      (node (ref "D62") (pin "2") (pinfunction "A_2") (pintype "passive"))
      (node (ref "D74") (pin "2") (pinfunction "A_2") (pintype "passive"))
      (node (ref "D86") (pin "2") (pinfunction "A_2") (pintype "passive"))
      (node (ref "Q3") (pin "3") (pinfunction "D_3") (pintype "passive"))
    )
    (net (code "4") (name "/COL_3") (class "Default")
      (node (ref "D15") (pin "2") (pinfunction "A_2") (pintype "passive"))
      (node (ref "D27") (pin "2") (pinfunction "A_2") (pintype "passive"))
      (node (ref "D3") (pin "2") (pinfunction "A_2") (pintype "passive"))
      (node (ref "D39") (pin "2") (pinfunction "A_2") (pintype "passive"))
      (node (ref "D51") (pin "2") (pinfunction "A_2") (pintype "passive"))
      (node (ref "D63") (pin "2") (pinfunction "A_2") (pintype "passive"))
      (node (ref "D75") (pin "2") (pinfunction "A_2") (pintype "passive"))
      (node (ref "D87") (pin "2") (pinfunction "A_2") (pintype "passive"))
      (node (ref "Q5") (pin "3") (pinfunction "D_3") (pintype "passive"))
    )
    (net (code "5") (name "/COL_4") (class "Default")
      (node (ref "D16") (pin "2") (pinfunction "A_2") (pintype "passive"))
      (node (ref "D28") (pin "2") (pinfunction "A_2") (pintype "passive"))
      (node (ref "D4") (pin "2") (pinfunction "A_2") (pintype "passive"))
      (node (ref "D40") (pin "2") (pinfunction "A_2") (pintype "passive"))
      (node (ref "D52") (pin "2") (pinfunction "A_2") (pintype "passive"))
      (node (ref "D64") (pin "2") (pinfunction "A_2") (pintype "passive"))
      (node (ref "D76") (pin "2") (pinfunction "A_2") (pintype "passive"))
      (node (ref "D88") (pin "2") (pinfunction "A_2") (pintype "passive"))
      (node (ref "Q7") (pin "3") (pinfunction "D_3") (pintype "passive"))
    )
    (net (code "6") (name "/COL_5") (class "Default")
      (node (ref "D17") (pin "2") (pinfunction "A_2") (pintype "passive"))
      (node (ref "D29") (pin "2") (pinfunction "A_2") (pintype "passive"))
      (node (ref "D41") (pin "2") (pinfunction "A_2") (pintype "passive"))
      (node (ref "D5") (pin "2") (pinfunction "A_2") (pintype "passive"))
      (node (ref "D53") (pin "2") (pinfunction "A_2") (pintype "passive"))
      (node (ref "D65") (pin "2") (pinfunction "A_2") (pintype "passive"))
      (node (ref "D77") (pin "2") (pinfunction "A_2") (pintype "passive"))
      (node (ref "D89") (pin "2") (pinfunction "A_2") (pintype "passive"))
      (node (ref "Q9") (pin "3") (pinfunction "D_3") (pintype "passive"))
    )
    (net (code "7") (name "/COL_6") (class "Default")
      (node (ref "D18") (pin "2") (pinfunction "A_2") (pintype "passive"))
      (node (ref "D30") (pin "2") (pinfunction "A_2") (pintype "passive"))
      (node (ref "D42") (pin "2") (pinfunction "A_2") (pintype "passive"))
      (node (ref "D54") (pin "2") (pinfunction "A_2") (pintype "passive"))
      (node (ref "D6") (pin "2") (pinfunction "A_2") (pintype "passive"))
      (node (ref "D66") (pin "2") (pinfunction "A_2") (pintype "passive"))
      (node (ref "D78") (pin "2") (pinfunction "A_2") (pintype "passive"))
      (node (ref "D90") (pin "2") (pinfunction "A_2") (pintype "passive"))
      (node (ref "Q11") (pin "3") (pinfunction "D_3") (pintype "passive"))
    )
    (net (code "8") (name "/COL_7") (class "Default")
      (node (ref "D19") (pin "2") (pinfunction "A_2") (pintype "passive"))
      (node (ref "D31") (pin "2") (pinfunction "A_2") (pintype "passive"))
      (node (ref "D43") (pin "2") (pinfunction "A_2") (pintype "passive"))
      (node (ref "D55") (pin "2") (pinfunction "A_2") (pintype "passive"))
      (node (ref "D67") (pin "2") (pinfunction "A_2") (pintype "passive"))
      (node (ref "D7") (pin "2") (pinfunction "A_2") (pintype "passive"))
      (node (ref "D79") (pin "2") (pinfunction "A_2") (pintype "passive"))
      (node (ref "D91") (pin "2") (pinfunction "A_2") (pintype "passive"))
      (node (ref "Q2") (pin "3") (pinfunction "D_3") (pintype "passive"))
    )
    (net (code "9") (name "/COL_8") (class "Default")
      (node (ref "D20") (pin "2") (pinfunction "A_2") (pintype "passive"))
      (node (ref "D32") (pin "2") (pinfunction "A_2") (pintype "passive"))
      (node (ref "D44") (pin "2") (pinfunction "A_2") (pintype "passive"))
      (node (ref "D56") (pin "2") (pinfunction "A_2") (pintype "passive"))
      (node (ref "D68") (pin "2") (pinfunction "A_2") (pintype "passive"))
      (node (ref "D8") (pin "2") (pinfunction "A_2") (pintype "passive"))
      (node (ref "D80") (pin "2") (pinfunction "A_2") (pintype "passive"))
      (node (ref "D92") (pin "2") (pinfunction "A_2") (pintype "passive"))
      (node (ref "Q4") (pin "3") (pinfunction "D_3") (pintype "passive"))
    )
    (net (code "10") (name "/COL_9") (class "Default")
      (node (ref "D21") (pin "2") (pinfunction "A_2") (pintype "passive"))
      (node (ref "D33") (pin "2") (pinfunction "A_2") (pintype "passive"))
      (node (ref "D45") (pin "2") (pinfunction "A_2") (pintype "passive"))
      (node (ref "D57") (pin "2") (pinfunction "A_2") (pintype "passive"))
      (node (ref "D69") (pin "2") (pinfunction "A_2") (pintype "passive"))
      (node (ref "D81") (pin "2") (pinfunction "A_2") (pintype "passive"))
      (node (ref "D9") (pin "2") (pinfunction "A_2") (pintype "passive"))
      (node (ref "D93") (pin "2") (pinfunction "A_2") (pintype "passive"))
      (node (ref "Q6") (pin "3") (pinfunction "D_3") (pintype "passive"))
    )
    (net (code "11") (name "/COL_10") (class "Default")
      (node (ref "D10") (pin "2") (pinfunction "A_2") (pintype "passive"))
      (node (ref "D22") (pin "2") (pinfunction "A_2") (pintype "passive"))
      (node (ref "D34") (pin "2") (pinfunction "A_2") (pintype "passive"))
      (node (ref "D46") (pin "2") (pinfunction "A_2") (pintype "passive"))
      (node (ref "D58") (pin "2") (pinfunction "A_2") (pintype "passive"))
      (node (ref "D70") (pin "2") (pinfunction "A_2") (pintype "passive"))
      (node (ref "D82") (pin "2") (pinfunction "A_2") (pintype "passive"))
      (node (ref "D94") (pin "2") (pinfunction "A_2") (pintype "passive"))
      (node (ref "Q8") (pin "3") (pinfunction "D_3") (pintype "passive"))
    )
    (net (code "12") (name "/COL_11") (class "Default")
      (node (ref "D11") (pin "2") (pinfunction "A_2") (pintype "passive"))
      (node (ref "D23") (pin "2") (pinfunction "A_2") (pintype "passive"))
      (node (ref "D35") (pin "2") (pinfunction "A_2") (pintype "passive"))
      (node (ref "D47") (pin "2") (pinfunction "A_2") (pintype "passive"))
      (node (ref "D59") (pin "2") (pinfunction "A_2") (pintype "passive"))
      (node (ref "D71") (pin "2") (pinfunction "A_2") (pintype "passive"))
      (node (ref "D83") (pin "2") (pinfunction "A_2") (pintype "passive"))
      (node (ref "D95") (pin "2") (pinfunction "A_2") (pintype "passive"))
      (node (ref "Q10") (pin "3") (pinfunction "D_3") (pintype "passive"))
    )
    (net (code "13") (name "/COL_12") (class "Default")
      (node (ref "D12") (pin "2") (pinfunction "A_2") (pintype "passive"))
      (node (ref "D24") (pin "2") (pinfunction "A_2") (pintype "passive"))
      (node (ref "D36") (pin "2") (pinfunction "A_2") (pintype "passive"))
      (node (ref "D48") (pin "2") (pinfunction "A_2") (pintype "passive"))
      (node (ref "D60") (pin "2") (pinfunction "A_2") (pintype "passive"))
      (node (ref "D72") (pin "2") (pinfunction "A_2") (pintype "passive"))
      (node (ref "D84") (pin "2") (pinfunction "A_2") (pintype "passive"))
      (node (ref "D96") (pin "2") (pinfunction "A_2") (pintype "passive"))
      (node (ref "Q12") (pin "3") (pinfunction "D_3") (pintype "passive"))
    )
    (net (code "14") (name "/COL_DS") (class "Default")
      (node (ref "H2") (pin "5") (pintype "passive"))
      (node (ref "U1") (pin "7") (pinfunction "IO7_7") (pintype "passive"))
      (node (ref "U4") (pin "14") (pinfunction "DS_14") (pintype "passive"))
    )
    (net (code "15") (name "/COL_OE") (class "Default")
      (node (ref "H2") (pin "4") (pintype "passive"))
      (node (ref "U1") (pin "6") (pinfunction "IO6_6") (pintype "passive"))
      (node (ref "U4") (pin "13") (pinfunction "~{OE}_13") (pintype "passive"))
      (node (ref "U5") (pin "13") (pinfunction "~{OE}_13") (pintype "passive"))
    )
    (net (code "16") (name "/COL_SH_CP") (class "Default")
      (node (ref "H2") (pin "2") (pintype "passive"))
      (node (ref "U1") (pin "4") (pinfunction "IO4_4") (pintype "passive"))
      (node (ref "U4") (pin "11") (pinfunction "SH_CP_11") (pintype "passive"))
      (node (ref "U5") (pin "11") (pinfunction "SH_CP_11") (pintype "passive"))
    )
    (net (code "17") (name "/COL_ST_CP") (class "Default")
      (node (ref "H2") (pin "3") (pintype "passive"))
      (node (ref "U1") (pin "5") (pinfunction "IO5_5") (pintype "passive"))
      (node (ref "U4") (pin "12") (pinfunction "ST_CP_12") (pintype "passive"))
      (node (ref "U5") (pin "12") (pinfunction "ST_CP_12") (pintype "passive"))
    )
    (net (code "18") (name "/EXT_SUPP_EN") (class "Default")
      (node (ref "R5") (pin "1") (pintype "passive"))
      (node (ref "U2") (pin "5") (pinfunction "ST_5") (pintype "passive"))
      (node (ref "U7") (pin "3") (pinfunction "~{CE}_3") (pintype "passive"))
    )
    (net (code "19") (name "/GPIO1") (class "Default")
      (node (ref "H3") (pin "1") (pintype "passive"))
      (node (ref "U1") (pin "39") (pinfunction "IO1_39") (pintype "passive"))
    )
    (net (code "20") (name "/GPIO2") (class "Default")
      (node (ref "H3") (pin "2") (pintype "passive"))
      (node (ref "U1") (pin "38") (pinfunction "IO2_38") (pintype "passive"))
    )
    (net (code "21") (name "/GPIO3") (class "Default")
      (node (ref "H4") (pin "1") (pintype "passive"))
      (node (ref "U1") (pin "15") (pinfunction "IO3_15") (pintype "passive"))
    )
    (net (code "22") (name "/GPIO8") (class "Default")
      (node (ref "H2") (pin "10") (pintype "passive"))
      (node (ref "U1") (pin "12") (pinfunction "IO8_12") (pintype "passive"))
    )
    (net (code "23") (name "/GPIO9") (class "Default")
      (node (ref "H4") (pin "3") (pintype "passive"))
      (node (ref "U1") (pin "17") (pinfunction "IO9_17") (pintype "passive"))
    )
    (net (code "24") (name "/GPIO10") (class "Default")
      (node (ref "H4") (pin "4") (pintype "passive"))
      (node (ref "U1") (pin "18") (pinfunction "IO10_18") (pintype "passive"))
    )
    (net (code "25") (name "/GPIO11") (class "Default")
      (node (ref "H4") (pin "5") (pintype "passive"))
      (node (ref "U1") (pin "19") (pinfunction "IO11_19") (pintype "passive"))
    )
    (net (code "26") (name "/GPIO12") (class "Default")
      (node (ref "H4") (pin "6") (pintype "passive"))
      (node (ref "U1") (pin "20") (pinfunction "IO12_20") (pintype "passive"))
    )
    (net (code "27") (name "/GPIO13") (class "Default")
      (node (ref "H4") (pin "7") (pintype "passive"))
      (node (ref "U1") (pin "21") (pinfunction "IO13_21") (pintype "passive"))
    )
    (net (code "28") (name "/GPIO14") (class "Default")
      (node (ref "H4") (pin "8") (pintype "passive"))
      (node (ref "U1") (pin "22") (pinfunction "IO14_22") (pintype "passive"))
    )
    (net (code "29") (name "/GPIO15") (class "Default")
      (node (ref "H2") (pin "6") (pintype "passive"))
      (node (ref "U1") (pin "8") (pinfunction "IO15_8") (pintype "passive"))
      (node (ref "U6") (pin "3") (pinfunction "CLK_3") (pintype "passive"))
    )
    (net (code "30") (name "/GPIO16") (class "Default")
      (node (ref "H2") (pin "7") (pintype "passive"))
      (node (ref "U1") (pin "9") (pinfunction "IO16_9") (pintype "passive"))
      (node (ref "U6") (pin "4") (pinfunction "LE/DM1_4") (pintype "passive"))
    )
    (net (code "31") (name "/GPIO17") (class "Default")
      (node (ref "H2") (pin "8") (pintype "passive"))
      (node (ref "U1") (pin "10") (pinfunction "IO17_10") (pintype "passive"))
      (node (ref "U6") (pin "13") (pinfunction "~{OE}/DM2_13") (pintype "passive"))
    )
    (net (code "32") (name "/GPIO18") (class "Default")
      (node (ref "H2") (pin "9") (pintype "passive"))
      (node (ref "U1") (pin "11") (pinfunction "IO18_11") (pintype "passive"))
      (node (ref "U6") (pin "2") (pinfunction "SDI_2") (pintype "passive"))
    )
    (net (code "33") (name "/GPIO19") (class "Default")
      (node (ref "H2") (pin "11") (pintype "passive"))
      (node (ref "R31") (pin "1") (pintype "passive"))
    )
    (net (code "34") (name "/GPIO20") (class "Default")
      (node (ref "H2") (pin "12") (pintype "passive"))
      (node (ref "R32") (pin "1") (pintype "passive"))
    )
    (net (code "35") (name "/GPIO21") (class "Default")
      (node (ref "H4") (pin "9") (pintype "passive"))
      (node (ref "U1") (pin "23") (pinfunction "IO21_23") (pintype "passive"))
    )
    (net (code "36") (name "/GPIO35") (class "Default")
      (node (ref "H3") (pin "12") (pintype "passive"))
      (node (ref "U1") (pin "28") (pinfunction "IO35_28") (pintype "passive"))
    )
    (net (code "37") (name "/GPIO36") (class "Default")
      (node (ref "H3") (pin "11") (pintype "passive"))
      (node (ref "U1") (pin "29") (pinfunction "IO36_29") (pintype "passive"))
    )
    (net (code "38") (name "/GPIO37") (class "Default")
      (node (ref "H3") (pin "10") (pintype "passive"))
      (node (ref "U1") (pin "30") (pinfunction "IO37_30") (pintype "passive"))
    )
    (net (code "39") (name "/GPIO38") (class "Default")
      (node (ref "H3") (pin "9") (pintype "passive"))
      (node (ref "U1") (pin "31") (pinfunction "IO38_31") (pintype "passive"))
    )
    (net (code "40") (name "/GPIO39") (class "Default")
      (node (ref "H3") (pin "8") (pintype "passive"))
      (node (ref "U1") (pin "32") (pinfunction "IO39_32") (pintype "passive"))
    )
    (net (code "41") (name "/GPIO40") (class "Default")
      (node (ref "H3") (pin "7") (pintype "passive"))
      (node (ref "U1") (pin "33") (pinfunction "IO40_33") (pintype "passive"))
    )
    (net (code "42") (name "/GPIO41") (class "Default")
      (node (ref "H3") (pin "6") (pintype "passive"))
      (node (ref "U1") (pin "34") (pinfunction "IO41_34") (pintype "passive"))
    )
    (net (code "43") (name "/GPIO42") (class "Default")
      (node (ref "H3") (pin "5") (pintype "passive"))
      (node (ref "U1") (pin "35") (pinfunction "IO42_35") (pintype "passive"))
    )
    (net (code "44") (name "/GPIO45") (class "Default")
      (node (ref "H4") (pin "12") (pintype "passive"))
      (node (ref "U1") (pin "26") (pinfunction "IO45_26") (pintype "passive"))
    )
    (net (code "45") (name "/GPIO46") (class "Default")
      (node (ref "H4") (pin "2") (pintype "passive"))
      (node (ref "U1") (pin "16") (pinfunction "IO46_16") (pintype "passive"))
    )
    (net (code "46") (name "/GPIO47") (class "Default")
      (node (ref "H4") (pin "10") (pintype "passive"))
      (node (ref "U1") (pin "24") (pinfunction "IO47_24") (pintype "passive"))
    )
    (net (code "47") (name "/GPIO48") (class "Default")
      (node (ref "H4") (pin "11") (pintype "passive"))
      (node (ref "U1") (pin "25") (pinfunction "IO48_25") (pintype "passive"))
    )
    (net (code "48") (name "/MCU_BOOT") (class "Default")
      (node (ref "SW2") (pin "3") (pintype "passive"))
      (node (ref "SW2") (pin "4") (pintype "passive"))
      (node (ref "U1") (pin "27") (pinfunction "IO0_27") (pintype "passive"))
    )
    (net (code "49") (name "/MCU_EN") (class "Default")
      (node (ref "C3") (pin "1") (pintype "passive"))
      (node (ref "R14") (pin "2") (pintype "passive"))
      (node (ref "SW1") (pin "3") (pintype "passive"))
      (node (ref "SW1") (pin "4") (pintype "passive"))
      (node (ref "U1") (pin "3") (pinfunction "EN_3") (pintype "passive"))
    )
    (net (code "50") (name "/ROW_1") (class "Default")
      (node (ref "D1") (pin "1") (pinfunction "K_1") (pintype "passive"))
      (node (ref "D10") (pin "1") (pinfunction "K_1") (pintype "passive"))
      (node (ref "D11") (pin "1") (pinfunction "K_1") (pintype "passive"))
      (node (ref "D12") (pin "1") (pinfunction "K_1") (pintype "passive"))
      (node (ref "D2") (pin "1") (pinfunction "K_1") (pintype "passive"))
      (node (ref "D3") (pin "1") (pinfunction "K_1") (pintype "passive"))
      (node (ref "D4") (pin "1") (pinfunction "K_1") (pintype "passive"))
      (node (ref "D5") (pin "1") (pinfunction "K_1") (pintype "passive"))
      (node (ref "D6") (pin "1") (pinfunction "K_1") (pintype "passive"))
      (node (ref "D7") (pin "1") (pinfunction "K_1") (pintype "passive"))
      (node (ref "D8") (pin "1") (pinfunction "K_1") (pintype "passive"))
      (node (ref "D9") (pin "1") (pinfunction "K_1") (pintype "passive"))
      (node (ref "U6") (pin "5") (pinfunction "OUT0_5") (pintype "passive"))
    )
    (net (code "51") (name "/ROW_2") (class "Default")
      (node (ref "D13") (pin "1") (pinfunction "K_1") (pintype "passive"))
      (node (ref "D14") (pin "1") (pinfunction "K_1") (pintype "passive"))
      (node (ref "D15") (pin "1") (pinfunction "K_1") (pintype "passive"))
      (node (ref "D16") (pin "1") (pinfunction "K_1") (pintype "passive"))
      (node (ref "D17") (pin "1") (pinfunction "K_1") (pintype "passive"))
      (node (ref "D18") (pin "1") (pinfunction "K_1") (pintype "passive"))
      (node (ref "D19") (pin "1") (pinfunction "K_1") (pintype "passive"))
      (node (ref "D20") (pin "1") (pinfunction "K_1") (pintype "passive"))
      (node (ref "D21") (pin "1") (pinfunction "K_1") (pintype "passive"))
      (node (ref "D22") (pin "1") (pinfunction "K_1") (pintype "passive"))
      (node (ref "D23") (pin "1") (pinfunction "K_1") (pintype "passive"))
      (node (ref "D24") (pin "1") (pinfunction "K_1") (pintype "passive"))
      (node (ref "U6") (pin "6") (pinfunction "OUT1_6") (pintype "passive"))
    )
    (net (code "52") (name "/ROW_3") (class "Default")
      (node (ref "D25") (pin "1") (pinfunction "K_1") (pintype "passive"))
      (node (ref "D26") (pin "1") (pinfunction "K_1") (pintype "passive"))
      (node (ref "D27") (pin "1") (pinfunction "K_1") (pintype "passive"))
      (node (ref "D28") (pin "1") (pinfunction "K_1") (pintype "passive"))
      (node (ref "D29") (pin "1") (pinfunction "K_1") (pintype "passive"))
      (node (ref "D30") (pin "1") (pinfunction "K_1") (pintype "passive"))
      (node (ref "D31") (pin "1") (pinfunction "K_1") (pintype "passive"))
      (node (ref "D32") (pin "1") (pinfunction "K_1") (pintype "passive"))
      (node (ref "D33") (pin "1") (pinfunction "K_1") (pintype "passive"))
      (node (ref "D34") (pin "1") (pinfunction "K_1") (pintype "passive"))
      (node (ref "D35") (pin "1") (pinfunction "K_1") (pintype "passive"))
      (node (ref "D36") (pin "1") (pinfunction "K_1") (pintype "passive"))
      (node (ref "U6") (pin "7") (pinfunction "OUT2_7") (pintype "passive"))
    )
    (net (code "53") (name "/ROW_4") (class "Default")
      (node (ref "D37") (pin "1") (pinfunction "K_1") (pintype "passive"))
      (node (ref "D38") (pin "1") (pinfunction "K_1") (pintype "passive"))
      (node (ref "D39") (pin "1") (pinfunction "K_1") (pintype "passive"))
      (node (ref "D40") (pin "1") (pinfunction "K_1") (pintype "passive"))
      (node (ref "D41") (pin "1") (pinfunction "K_1") (pintype "passive"))
      (node (ref "D42") (pin "1") (pinfunction "K_1") (pintype "passive"))
      (node (ref "D43") (pin "1") (pinfunction "K_1") (pintype "passive"))
      (node (ref "D44") (pin "1") (pinfunction "K_1") (pintype "passive"))
      (node (ref "D45") (pin "1") (pinfunction "K_1") (pintype "passive"))
      (node (ref "D46") (pin "1") (pinfunction "K_1") (pintype "passive"))
      (node (ref "D47") (pin "1") (pinfunction "K_1") (pintype "passive"))
      (node (ref "D48") (pin "1") (pinfunction "K_1") (pintype "passive"))
      (node (ref "U6") (pin "8") (pinfunction "OUT3_8") (pintype "passive"))
    )
    (net (code "54") (name "/ROW_5") (class "Default")
      (node (ref "D49") (pin "1") (pinfunction "K_1") (pintype "passive"))
      (node (ref "D50") (pin "1") (pinfunction "K_1") (pintype "passive"))
      (node (ref "D51") (pin "1") (pinfunction "K_1") (pintype "passive"))
      (node (ref "D52") (pin "1") (pinfunction "K_1") (pintype "passive"))
      (node (ref "D53") (pin "1") (pinfunction "K_1") (pintype "passive"))
      (node (ref "D54") (pin "1") (pinfunction "K_1") (pintype "passive"))
      (node (ref "D55") (pin "1") (pinfunction "K_1") (pintype "passive"))
      (node (ref "D56") (pin "1") (pinfunction "K_1") (pintype "passive"))
      (node (ref "D57") (pin "1") (pinfunction "K_1") (pintype "passive"))
      (node (ref "D58") (pin "1") (pinfunction "K_1") (pintype "passive"))
      (node (ref "D59") (pin "1") (pinfunction "K_1") (pintype "passive"))
      (node (ref "D60") (pin "1") (pinfunction "K_1") (pintype "passive"))
      (node (ref "U6") (pin "9") (pinfunction "OUT4_9") (pintype "passive"))
    )
    (net (code "55") (name "/ROW_6") (class "Default")
      (node (ref "D61") (pin "1") (pinfunction "K_1") (pintype "passive"))
      (node (ref "D62") (pin "1") (pinfunction "K_1") (pintype "passive"))
      (node (ref "D63") (pin "1") (pinfunction "K_1") (pintype "passive"))
      (node (ref "D64") (pin "1") (pinfunction "K_1") (pintype "passive"))
      (node (ref "D65") (pin "1") (pinfunction "K_1") (pintype "passive"))
      (node (ref "D66") (pin "1") (pinfunction "K_1") (pintype "passive"))
      (node (ref "D67") (pin "1") (pinfunction "K_1") (pintype "passive"))
      (node (ref "D68") (pin "1") (pinfunction "K_1") (pintype "passive"))
      (node (ref "D69") (pin "1") (pinfunction "K_1") (pintype "passive"))
      (node (ref "D70") (pin "1") (pinfunction "K_1") (pintype "passive"))
      (node (ref "D71") (pin "1") (pinfunction "K_1") (pintype "passive"))
      (node (ref "D72") (pin "1") (pinfunction "K_1") (pintype "passive"))
      (node (ref "U6") (pin "10") (pinfunction "OUT5_10") (pintype "passive"))
    )
    (net (code "56") (name "/ROW_7") (class "Default")
      (node (ref "D73") (pin "1") (pinfunction "K_1") (pintype "passive"))
      (node (ref "D74") (pin "1") (pinfunction "K_1") (pintype "passive"))
      (node (ref "D75") (pin "1") (pinfunction "K_1") (pintype "passive"))
      (node (ref "D76") (pin "1") (pinfunction "K_1") (pintype "passive"))
      (node (ref "D77") (pin "1") (pinfunction "K_1") (pintype "passive"))
      (node (ref "D78") (pin "1") (pinfunction "K_1") (pintype "passive"))
      (node (ref "D79") (pin "1") (pinfunction "K_1") (pintype "passive"))
      (node (ref "D80") (pin "1") (pinfunction "K_1") (pintype "passive"))
      (node (ref "D81") (pin "1") (pinfunction "K_1") (pintype "passive"))
      (node (ref "D82") (pin "1") (pinfunction "K_1") (pintype "passive"))
      (node (ref "D83") (pin "1") (pinfunction "K_1") (pintype "passive"))
      (node (ref "D84") (pin "1") (pinfunction "K_1") (pintype "passive"))
      (node (ref "U6") (pin "11") (pinfunction "OUT6_11") (pintype "passive"))
    )
    (net (code "57") (name "/ROW_8") (class "Default")
      (node (ref "D85") (pin "1") (pinfunction "K_1") (pintype "passive"))
      (node (ref "D86") (pin "1") (pinfunction "K_1") (pintype "passive"))
      (node (ref "D87") (pin "1") (pinfunction "K_1") (pintype "passive"))
      (node (ref "D88") (pin "1") (pinfunction "K_1") (pintype "passive"))
      (node (ref "D89") (pin "1") (pinfunction "K_1") (pintype "passive"))
      (node (ref "D90") (pin "1") (pinfunction "K_1") (pintype "passive"))
      (node (ref "D91") (pin "1") (pinfunction "K_1") (pintype "passive"))
      (node (ref "D92") (pin "1") (pinfunction "K_1") (pintype "passive"))
      (node (ref "D93") (pin "1") (pinfunction "K_1") (pintype "passive"))
      (node (ref "D94") (pin "1") (pinfunction "K_1") (pintype "passive"))
      (node (ref "D95") (pin "1") (pinfunction "K_1") (pintype "passive"))
      (node (ref "D96") (pin "1") (pinfunction "K_1") (pintype "passive"))
      (node (ref "U6") (pin "12") (pinfunction "OUT7_12") (pintype "passive"))
    )
    (net (code "58") (name "/SIG_COL_1") (class "Default")
      (node (ref "R3") (pin "1") (pintype "passive"))
      (node (ref "U4") (pin "1") (pinfunction "Q1_1") (pintype "passive"))
    )
    (net (code "59") (name "/SIG_COL_2") (class "Default")
      (node (ref "R8") (pin "1") (pintype "passive"))
      (node (ref "U4") (pin "2") (pinfunction "Q2_2") (pintype "passive"))
    )
    (net (code "60") (name "/SIG_COL_3") (class "Default")
      (node (ref "R12") (pin "1") (pintype "passive"))
      (node (ref "U4") (pin "3") (pinfunction "Q3_3") (pintype "passive"))
    )
    (net (code "61") (name "/SIG_COL_4") (class "Default")
      (node (ref "R17") (pin "1") (pintype "passive"))
      (node (ref "U4") (pin "4") (pinfunction "Q4_4") (pintype "passive"))
    )
    (net (code "62") (name "/SIG_COL_5") (class "Default")
      (node (ref "R21") (pin "1") (pintype "passive"))
      (node (ref "U4") (pin "5") (pinfunction "Q5_5") (pintype "passive"))
    )
    (net (code "63") (name "/SIG_COL_6") (class "Default")
      (node (ref "R25") (pin "1") (pintype "passive"))
      (node (ref "U4") (pin "6") (pinfunction "Q6_6") (pintype "passive"))
    )
    (net (code "64") (name "/SIG_COL_7") (class "Default")
      (node (ref "R4") (pin "1") (pintype "passive"))
      (node (ref "U4") (pin "7") (pinfunction "Q7_7") (pintype "passive"))
    )
    (net (code "65") (name "/SIG_COL_8") (class "Default")
      (node (ref "R9") (pin "1") (pintype "passive"))
      (node (ref "U5") (pin "1") (pinfunction "Q1_1") (pintype "passive"))
    )
    (net (code "66") (name "/SIG_COL_9") (class "Default")
      (node (ref "R13") (pin "1") (pintype "passive"))
      (node (ref "U5") (pin "2") (pinfunction "Q2_2") (pintype "passive"))
    )
    (net (code "67") (name "/SIG_COL_10") (class "Default")
      (node (ref "R18") (pin "1") (pintype "passive"))
      (node (ref "U5") (pin "3") (pinfunction "Q3_3") (pintype "passive"))
    )
    (net (code "68") (name "/SIG_COL_11") (class "Default")
      (node (ref "R22") (pin "1") (pintype "passive"))
      (node (ref "U5") (pin "4") (pinfunction "Q4_4") (pintype "passive"))
    )
    (net (code "69") (name "/SIG_COL_12") (class "Default")
      (node (ref "R26") (pin "1") (pintype "passive"))
      (node (ref "U5") (pin "5") (pinfunction "Q5_5") (pintype "passive"))
    )
    (net (code "70") (name "/UPDI_RX") (class "Default")
      (node (ref "H3") (pin "4") (pintype "passive"))
      (node (ref "R33") (pin "1") (pintype "passive"))
      (node (ref "U1") (pin "36") (pinfunction "RXD0_36") (pintype "passive"))
    )
    (net (code "71") (name "/UPDI_TX") (class "Default")
      (node (ref "H3") (pin "3") (pintype "passive"))
      (node (ref "R34") (pin "1") (pintype "passive"))
      (node (ref "U1") (pin "37") (pinfunction "TXD0_37") (pintype "passive"))
    )
    (net (code "72") (name "/USB_D_N") (class "Default")
      (node (ref "J1") (pin "10") (pinfunction "B7_10") (pintype "passive"))
      (node (ref "J1") (pin "8") (pinfunction "A7_8") (pintype "passive"))
      (node (ref "R31") (pin "2") (pintype "passive"))
      (node (ref "U1") (pin "13") (pinfunction "IO19_13") (pintype "passive"))
    )
    (net (code "73") (name "/USB_D_P") (class "Default")
      (node (ref "J1") (pin "7") (pinfunction "B6_7") (pintype "passive"))
      (node (ref "J1") (pin "9") (pinfunction "A6_9") (pintype "passive"))
      (node (ref "R32") (pin "2") (pintype "passive"))
      (node (ref "U1") (pin "14") (pinfunction "IO20_14") (pintype "passive"))
    )
    (net (code "74") (name "/USB_SUPP_EN") (class "Default")
      (node (ref "C5") (pin "1") (pintype "passive"))
      (node (ref "U2") (pin "3") (pinfunction "~{CE}_3") (pintype "passive"))
      (node (ref "U3") (pin "3") (pinfunction "VOUT_3") (pintype "passive"))
      (node (ref "U7") (pin "1") (pinfunction "VIN_1") (pintype "passive"))
    )
    (net (code "75") (name "GND") (class "Default")
      (node (ref "C1") (pin "2") (pintype "passive"))
      (node (ref "C2") (pin "2") (pintype "passive"))
      (node (ref "C3") (pin "2") (pintype "passive"))
      (node (ref "C4") (pin "2") (pintype "passive"))
      (node (ref "C5") (pin "2") (pintype "passive"))
      (node (ref "C6") (pin "2") (pintype "passive"))
      (node (ref "C7") (pin "2") (pintype "passive"))
      (node (ref "C8") (pin "2") (pintype "passive"))
      (node (ref "C9") (pin "2") (pintype "passive"))
      (node (ref "H1") (pin "1") (pintype "passive"))
      (node (ref "H1") (pin "3") (pintype "passive"))
      (node (ref "H1") (pin "5") (pintype "passive"))
      (node (ref "H1") (pin "6") (pintype "passive"))
      (node (ref "H1") (pin "8") (pintype "passive"))
      (node (ref "H5") (pin "4") (pintype "passive"))
      (node (ref "H7") (pin "1") (pintype "passive"))
      (node (ref "H7") (pin "2") (pintype "passive"))
      (node (ref "H7") (pin "3") (pintype "passive"))
      (node (ref "H7") (pin "4") (pintype "passive"))
      (node (ref "J1") (pin "1") (pinfunction "MH3_1") (pintype "passive"))
      (node (ref "J1") (pin "14") (pinfunction "A1_14") (pintype "passive"))
      (node (ref "J1") (pin "15") (pinfunction "MH1_15") (pintype "passive"))
      (node (ref "J1") (pin "16") (pinfunction "MH2_16") (pintype "passive"))
      (node (ref "J1") (pin "2") (pinfunction "MH4_2") (pintype "passive"))
      (node (ref "J1") (pin "3") (pinfunction "B1_3") (pintype "passive"))
      (node (ref "R27") (pin "1") (pintype "passive"))
      (node (ref "R28") (pin "1") (pintype "passive"))
      (node (ref "R30") (pin "3") (pintype "passive"))
      (node (ref "SW1") (pin "1") (pintype "passive"))
      (node (ref "SW1") (pin "2") (pintype "passive"))
      (node (ref "SW2") (pin "1") (pintype "passive"))
      (node (ref "SW2") (pin "2") (pintype "passive"))
      (node (ref "U1") (pin "1") (pinfunction "GND_1") (pintype "passive"))
      (node (ref "U1") (pin "40") (pinfunction "GND_40") (pintype "passive"))
      (node (ref "U1") (pin "41") (pinfunction "GND_41") (pintype "passive"))
      (node (ref "U1") (pin "42") (pinfunction "GND_42") (pintype "passive"))
      (node (ref "U1") (pin "43") (pinfunction "GND_43") (pintype "passive"))
      (node (ref "U1") (pin "44") (pinfunction "GND_44") (pintype "passive"))
      (node (ref "U1") (pin "45") (pinfunction "GND_45") (pintype "passive"))
      (node (ref "U1") (pin "46") (pinfunction "GND_46") (pintype "passive"))
      (node (ref "U1") (pin "47") (pinfunction "GND_47") (pintype "passive"))
      (node (ref "U1") (pin "48") (pinfunction "GND_48") (pintype "passive"))
      (node (ref "U1") (pin "49") (pinfunction "GND_49") (pintype "passive"))
      (node (ref "U2") (pin "2") (pinfunction "GND_2") (pintype "passive"))
      (node (ref "U3") (pin "2") (pinfunction "GND_2") (pintype "passive"))
      (node (ref "U3") (pin "4") (pinfunction "TAB_4") (pintype "passive"))
      (node (ref "U4") (pin "8") (pinfunction "GND_8") (pintype "passive"))
      (node (ref "U5") (pin "8") (pinfunction "GND_8") (pintype "passive"))
      (node (ref "U6") (pin "1") (pinfunction "GND_1") (pintype "passive"))
      (node (ref "U7") (pin "2") (pinfunction "GND_2") (pintype "passive"))
      (node (ref "U7") (pin "5") (pinfunction "ST_5") (pintype "passive"))
    )
    (net (code "76") (name "Net-(H5-Pad2)") (class "Default")
      (node (ref "H5") (pin "2") (pintype "passive"))
      (node (ref "R33") (pin "2") (pintype "passive"))
    )
    (net (code "77") (name "Net-(H5-Pad3)") (class "Default")
      (node (ref "H5") (pin "3") (pintype "passive"))
      (node (ref "R34") (pin "2") (pintype "passive"))
    )
    (net (code "78") (name "Net-(J1-A4)") (class "Default")
      (node (ref "C4") (pin "1") (pintype "passive"))
      (node (ref "J1") (pin "13") (pinfunction "A4_13") (pintype "passive"))
      (node (ref "J1") (pin "4") (pinfunction "B4_4") (pintype "passive"))
      (node (ref "U3") (pin "1") (pinfunction "VIN_1") (pintype "passive"))
    )
    (net (code "79") (name "Net-(J1-A5)") (class "Default")
      (node (ref "J1") (pin "11") (pinfunction "A5_11") (pintype "passive"))
      (node (ref "R28") (pin "2") (pintype "passive"))
    )
    (net (code "80") (name "Net-(J1-B5)") (class "Default")
      (node (ref "J1") (pin "5") (pinfunction "B5_5") (pintype "passive"))
      (node (ref "R27") (pin "2") (pintype "passive"))
    )
    (net (code "81") (name "Net-(Q1-G)") (class "Default")
      (node (ref "Q1") (pin "1") (pinfunction "G_1") (pintype "passive"))
      (node (ref "R1") (pin "2") (pintype "passive"))
      (node (ref "R3") (pin "2") (pintype "passive"))
    )
    (net (code "82") (name "Net-(Q2-G)") (class "Default")
      (node (ref "Q2") (pin "1") (pinfunction "G_1") (pintype "passive"))
      (node (ref "R2") (pin "2") (pintype "passive"))
      (node (ref "R4") (pin "2") (pintype "passive"))
    )
    (net (code "83") (name "Net-(Q3-G)") (class "Default")
      (node (ref "Q3") (pin "1") (pinfunction "G_1") (pintype "passive"))
      (node (ref "R6") (pin "2") (pintype "passive"))
      (node (ref "R8") (pin "2") (pintype "passive"))
    )
    (net (code "84") (name "Net-(Q4-G)") (class "Default")
      (node (ref "Q4") (pin "1") (pinfunction "G_1") (pintype "passive"))
      (node (ref "R7") (pin "2") (pintype "passive"))
      (node (ref "R9") (pin "2") (pintype "passive"))
    )
    (net (code "85") (name "Net-(Q5-G)") (class "Default")
      (node (ref "Q5") (pin "1") (pinfunction "G_1") (pintype "passive"))
      (node (ref "R10") (pin "2") (pintype "passive"))
      (node (ref "R12") (pin "2") (pintype "passive"))
    )
    (net (code "86") (name "Net-(Q6-G)") (class "Default")
      (node (ref "Q6") (pin "1") (pinfunction "G_1") (pintype "passive"))
      (node (ref "R11") (pin "2") (pintype "passive"))
      (node (ref "R13") (pin "2") (pintype "passive"))
    )
    (net (code "87") (name "Net-(Q7-G)") (class "Default")
      (node (ref "Q7") (pin "1") (pinfunction "G_1") (pintype "passive"))
      (node (ref "R15") (pin "2") (pintype "passive"))
      (node (ref "R17") (pin "2") (pintype "passive"))
    )
    (net (code "88") (name "Net-(Q8-G)") (class "Default")
      (node (ref "Q8") (pin "1") (pinfunction "G_1") (pintype "passive"))
      (node (ref "R16") (pin "2") (pintype "passive"))
      (node (ref "R18") (pin "2") (pintype "passive"))
    )
    (net (code "89") (name "Net-(Q9-G)") (class "Default")
      (node (ref "Q9") (pin "1") (pinfunction "G_1") (pintype "passive"))
      (node (ref "R19") (pin "2") (pintype "passive"))
      (node (ref "R21") (pin "2") (pintype "passive"))
    )
    (net (code "90") (name "Net-(Q10-G)") (class "Default")
      (node (ref "Q10") (pin "1") (pinfunction "G_1") (pintype "passive"))
      (node (ref "R20") (pin "2") (pintype "passive"))
      (node (ref "R22") (pin "2") (pintype "passive"))
    )
    (net (code "91") (name "Net-(Q11-G)") (class "Default")
      (node (ref "Q11") (pin "1") (pinfunction "G_1") (pintype "passive"))
      (node (ref "R23") (pin "2") (pintype "passive"))
      (node (ref "R25") (pin "2") (pintype "passive"))
    )
    (net (code "92") (name "Net-(Q12-G)") (class "Default")
      (node (ref "Q12") (pin "1") (pinfunction "G_1") (pintype "passive"))
      (node (ref "R24") (pin "2") (pintype "passive"))
      (node (ref "R26") (pin "2") (pintype "passive"))
    )
    (net (code "93") (name "Net-(R29-Pad2)") (class "Default")
      (node (ref "R29") (pin "2") (pintype "passive"))
      (node (ref "R30") (pin "1") (pintype "passive"))
      (node (ref "R30") (pin "2") (pintype "passive"))
    )
    (net (code "94") (name "Net-(U4-Q7')") (class "Default")
      (node (ref "U4") (pin "9") (pinfunction "Q7'_9") (pintype "passive"))
      (node (ref "U5") (pin "14") (pinfunction "DS_14") (pintype "passive"))
    )
    (net (code "95") (name "Net-(U6-R-EXT)") (class "Default")
      (node (ref "R29") (pin "1") (pintype "passive"))
      (node (ref "U6") (pin "15") (pinfunction "R-EXT_15") (pintype "passive"))
    )
    (net (code "96") (name "VCC_1") (class "Default")
      (node (ref "H1") (pin "2") (pintype "passive"))
      (node (ref "Q1") (pin "2") (pinfunction "S_2") (pintype "passive"))
      (node (ref "Q10") (pin "2") (pinfunction "S_2") (pintype "passive"))
      (node (ref "Q11") (pin "2") (pinfunction "S_2") (pintype "passive"))
      (node (ref "Q12") (pin "2") (pinfunction "S_2") (pintype "passive"))
      (node (ref "Q2") (pin "2") (pinfunction "S_2") (pintype "passive"))
      (node (ref "Q3") (pin "2") (pinfunction "S_2") (pintype "passive"))
      (node (ref "Q4") (pin "2") (pinfunction "S_2") (pintype "passive"))
      (node (ref "Q5") (pin "2") (pinfunction "S_2") (pintype "passive"))
      (node (ref "Q6") (pin "2") (pinfunction "S_2") (pintype "passive"))
      (node (ref "Q7") (pin "2") (pinfunction "S_2") (pintype "passive"))
      (node (ref "Q8") (pin "2") (pinfunction "S_2") (pintype "passive"))
      (node (ref "Q9") (pin "2") (pinfunction "S_2") (pintype "passive"))
      (node (ref "R1") (pin "1") (pintype "passive"))
      (node (ref "R10") (pin "1") (pintype "passive"))
      (node (ref "R11") (pin "1") (pintype "passive"))
      (node (ref "R15") (pin "1") (pintype "passive"))
      (node (ref "R16") (pin "1") (pintype "passive"))
      (node (ref "R19") (pin "1") (pintype "passive"))
      (node (ref "R2") (pin "1") (pintype "passive"))
      (node (ref "R20") (pin "1") (pintype "passive"))
      (node (ref "R23") (pin "1") (pintype "passive"))
      (node (ref "R24") (pin "1") (pintype "passive"))
      (node (ref "R6") (pin "1") (pintype "passive"))
      (node (ref "R7") (pin "1") (pintype "passive"))
    )
    (net (code "97") (name "VCC_2") (class "Default") (node (ref "H1") (pin "4") (pintype "passive")))
    (net (code "98") (name "V_MCU") (class "Default")
      (node (ref "H1") (pin "7") (pintype "passive"))
      (node (ref "R5") (pin "2") (pintype "passive"))
      (node (ref "U2") (pin "1") (pinfunction "VIN_1") (pintype "passive"))
    )
    (net (code "99") (name "unconnected-(J1-A8-Pad6)") (class "Default")
      (node (ref "J1") (pin "6") (pinfunction "A8_6") (pintype "passive+no_connect"))
    )
    (net (code "100") (name "unconnected-(J1-B8-Pad12)") (class "Default")
      (node (ref "J1") (pin "12") (pinfunction "B8_12") (pintype "passive+no_connect"))
    )
    (net (code "101") (name "unconnected-(U2-N{slash}C-Pad4)") (class "Default")
      (node (ref "U2") (pin "4") (pinfunction "N/C_4") (pintype "passive+no_connect"))
    )
    (net (code "102") (name "unconnected-(U4-Q0-Pad15)") (class "Default")
      (node (ref "U4") (pin "15") (pinfunction "Q0_15") (pintype "passive+no_connect"))
    )
    (net (code "103") (name "unconnected-(U5-Q0-Pad15)") (class "Default")
      (node (ref "U5") (pin "15") (pinfunction "Q0_15") (pintype "passive+no_connect"))
    )
    (net (code "104") (name "unconnected-(U5-Q6-Pad6)") (class "Default")
      (node (ref "U5") (pin "6") (pinfunction "Q6_6") (pintype "passive+no_connect"))
    )
    (net (code "105") (name "unconnected-(U5-Q7'-Pad9)") (class "Default")
      (node (ref "U5") (pin "9") (pinfunction "Q7'_9") (pintype "passive+no_connect"))
    )
    (net (code "106") (name "unconnected-(U5-Q7-Pad7)") (class "Default")
      (node (ref "U5") (pin "7") (pinfunction "Q7_7") (pintype "passive+no_connect"))
    )
    (net (code "107") (name "unconnected-(U6-SDO-Pad14)") (class "Default")
      (node (ref "U6") (pin "14") (pinfunction "SDO_14") (pintype "passive+no_connect"))
    )
    (net (code "108") (name "unconnected-(U7-N{slash}C-Pad4)") (class "Default")
      (node (ref "U7") (pin "4") (pinfunction "N/C_4") (pintype "passive+no_connect"))
    )
  )
)
